# MC34063_Through_hole.net
KiCad netlist of a schematic drawn in EAGLE
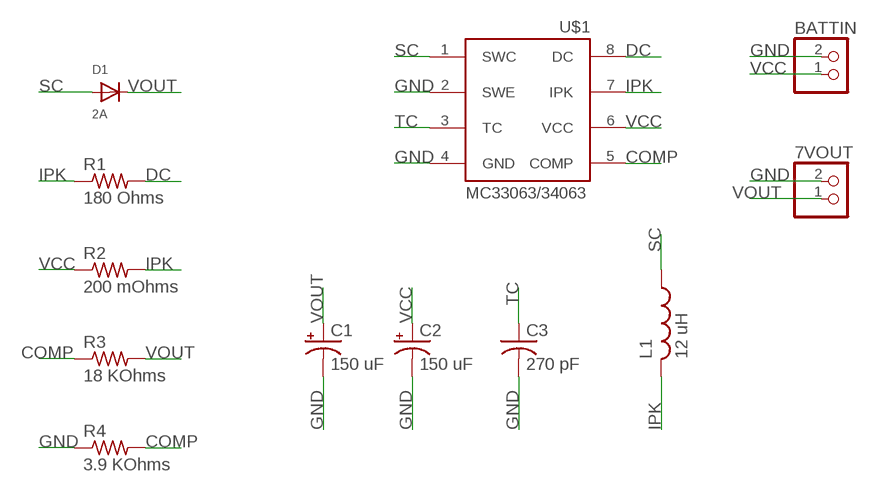
[diagram p0: schematic, sheet 1]

(export (version "E")
  (design (tool "Eeschema 10.0.6"))
  (components
    (comp (ref "7VOUT")
      (value "JST_2PIN-THM-RA")
      (footprint "eagle-import:JST-PH-2-THM-RA")
      (libsource (lib "eagle-import") (part "JST_2PIN-THM-RA"))
    )
    (comp (ref "BATTIN")
      (value "JST_2PIN-THM-RA")
      (footprint "eagle-import:JST-PH-2-THM-RA")
      (libsource (lib "eagle-import") (part "JST_2PIN-THM-RA"))
    )
    (comp (ref "C1")
      (value "150 uF")
      (footprint "eagle-import:E2-5")
      (libsource (lib "eagle-import") (part "CPOL-USE2-5"))
    )
    (comp (ref "C2")
      (value "150 uF")
      (footprint "eagle-import:E2-5")
      (libsource (lib "eagle-import") (part "CPOL-USE2-5"))
    )
    (comp (ref "C3")
      (value "270 pF")
      (footprint "eagle-import:C050-024X044")
      (libsource (lib "eagle-import") (part "C-US050-024X044"))
    )
    (comp (ref "D1")
      (value "2A")
      (footprint "eagle-import:DO-1N4148")
      (libsource (lib "eagle-import") (part "DIODEDO-1N4148"))
    )
    (comp (ref "L1")
      (value "12 uH")
      (footprint "eagle-import:0207_5V")
      (libsource (lib "eagle-import") (part "L-US0207/5V"))
    )
    (comp (ref "R1")
      (value "180 Ohms")
      (footprint "eagle-import:0207_2V")
      (libsource (lib "eagle-import") (part "R-US_0207/2V"))
    )
    (comp (ref "R2")
      (value "200 mOhms")
      (footprint "eagle-import:0207_2V")
      (libsource (lib "eagle-import") (part "R-US_0207/2V"))
    )
    (comp (ref "R3")
      (value "18 KOhms")
      (footprint "eagle-import:0207_2V")
      (libsource (lib "eagle-import") (part "R-US_0207/2V"))
    )
    (comp (ref "R4")
      (value "3.9 KOhms")
      (footprint "eagle-import:0207_2V")
      (libsource (lib "eagle-import") (part "R-US_0207/2V"))
    )
    (comp (ref "U$1")
      (value "MC33063/MC34063P")
      (footprint "eagle-import:DIL08")
      (libsource (lib "eagle-import") (part "MC33063/MC34063P"))
    )
  )
  (nets
    (net (code "1") (name "/COMP") (class "Default")
      (node (ref "R3") (pin "1") (pinfunction "1_1") (pintype "passive"))
      (node (ref "R4") (pin "2") (pinfunction "2_2") (pintype "passive"))
      (node (ref "U$1") (pin "5") (pinfunction "COMP_5") (pintype "input"))
    )
    (net (code "2") (name "/DC") (class "Default")
      (node (ref "R1") (pin "2") (pinfunction "2_2") (pintype "passive"))
      (node (ref "U$1") (pin "8") (pinfunction "DC_8") (pintype "input"))
    )
    (net (code "3") (name "/GND") (class "Default")
      (node (ref "7VOUT") (pin "2") (pinfunction "1_2") (pintype "passive"))
      (node (ref "BATTIN") (pin "2") (pinfunction "1_2") (pintype "passive"))
      (node (ref "C1") (pin "-") (pinfunction "-_-") (pintype "passive"))
      (node (ref "C2") (pin "-") (pinfunction "-_-") (pintype "passive"))
      (node (ref "C3") (pin "2") (pinfunction "2_2") (pintype "passive"))
      (node (ref "R4") (pin "1") (pinfunction "1_1") (pintype "passive"))
      (node (ref "U$1") (pin "2") (pinfunction "SWE_2") (pintype "input"))
      (node (ref "U$1") (pin "4") (pinfunction "GND_4") (pintype "power_in"))
    )
    (net (code "4") (name "/IPK") (class "Default")
      (node (ref "L1") (pin "2") (pinfunction "2_2") (pintype "passive"))
      (node (ref "R1") (pin "1") (pinfunction "1_1") (pintype "passive"))
      (node (ref "R2") (pin "2") (pinfunction "2_2") (pintype "passive"))
      (node (ref "U$1") (pin "7") (pinfunction "IPK_7") (pintype "bidirectional"))
    )
    (net (code "5") (name "/SC") (class "Default")
      (node (ref "D1") (pin "A") (pinfunction "A_A") (pintype "passive"))
      (node (ref "L1") (pin "1") (pinfunction "1_1") (pintype "passive"))
      (node (ref "U$1") (pin "1") (pinfunction "SWC_1") (pintype "input"))
    )
    (net (code "6") (name "/TC") (class "Default")
      (node (ref "C3") (pin "1") (pinfunction "1_1") (pintype "passive"))
      (node (ref "U$1") (pin "3") (pinfunction "TC_3") (pintype "input"))
    )
    (net (code "7") (name "/VCC") (class "Default")
      (node (ref "BATTIN") (pin "1") (pinfunction "2_1") (pintype "passive"))
      (node (ref "C2") (pin "+") (pinfunction "+_+") (pintype "passive"))
      (node (ref "R2") (pin "1") (pinfunction "1_1") (pintype "passive"))
      (node (ref "U$1") (pin "6") (pinfunction "VCC_6") (pintype "power_in"))
    )
    (net (code "8") (name "/VOUT") (class "Default")
      (node (ref "7VOUT") (pin "1") (pinfunction "2_1") (pintype "passive"))
      (node (ref "C1") (pin "+") (pinfunction "+_+") (pintype "passive"))
      (node (ref "D1") (pin "C") (pinfunction "C_C") (pintype "passive"))
      (node (ref "R3") (pin "2") (pinfunction "2_2") (pintype "passive"))
    )
  )
)
